# ports.net
KiCad netlist of a schematic drawn in Altium Designer
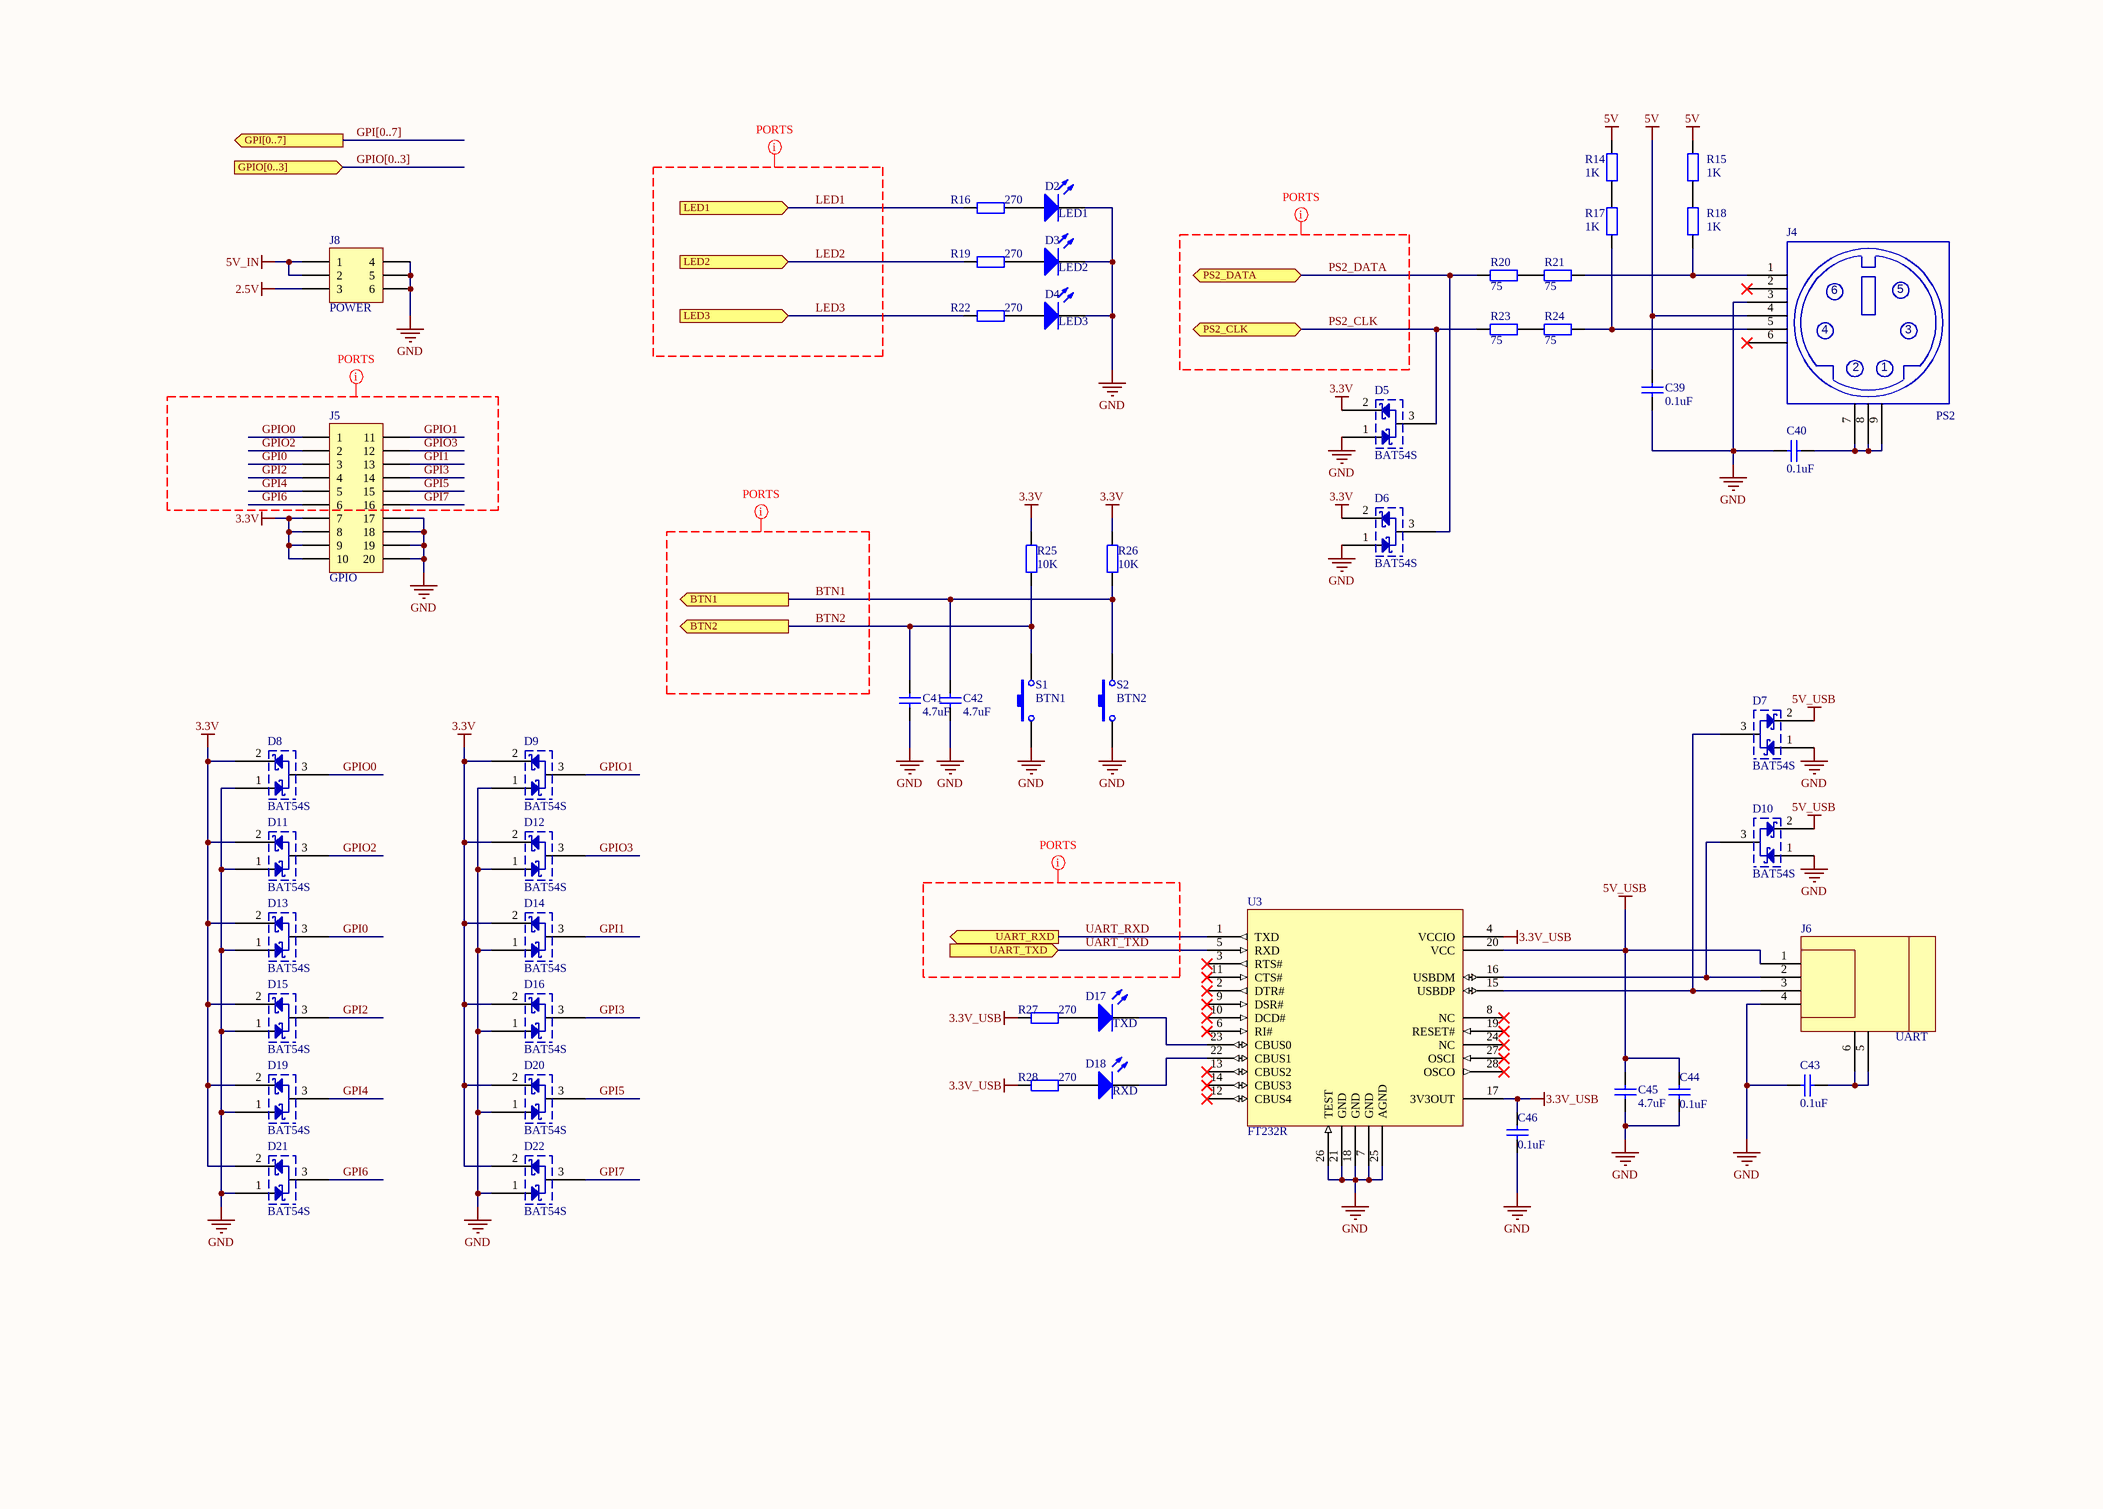
[diagram p0: ports.SchDoc]

(export (version "E")
  (design (tool "Eeschema 10.0.6"))
  (components
    (comp (ref "C39")
      (value "0.1uF")
      (footprint "0402")
      (description "Capacitor")
      (fields (field (name "Comment") "Cap") (field (name "PUBLISHER") "Altium Limited"))
      (libsource (lib "Miscellaneous Devices") (part "Cap"))
    )
    (comp (ref "C40")
      (value "0.1uF")
      (footprint "0402")
      (description "Capacitor")
      (fields (field (name "Comment") "Cap") (field (name "PUBLISHER") "Altium Limited"))
      (libsource (lib "Miscellaneous Devices") (part "Cap"))
    )
    (comp (ref "C41")
      (value "4.7uF")
      (footprint "C0805")
      (description "Capacitor")
      (fields (field (name "Comment") "Cap") (field (name "PUBLISHER") "Altium Limited"))
      (libsource (lib "Miscellaneous Devices") (part "Cap"))
    )
    (comp (ref "C42")
      (value "4.7uF")
      (footprint "C0805")
      (description "Capacitor")
      (fields (field (name "Comment") "Cap") (field (name "PUBLISHER") "Altium Limited"))
      (libsource (lib "Miscellaneous Devices") (part "Cap"))
    )
    (comp (ref "C43")
      (value "0.1uF")
      (footprint "0402")
      (description "Capacitor")
      (fields (field (name "Comment") "Cap") (field (name "PUBLISHER") "Altium Limited"))
      (libsource (lib "Miscellaneous Devices") (part "Cap"))
    )
    (comp (ref "C44")
      (value "0.1uF")
      (footprint "0402")
      (description "Capacitor")
      (fields (field (name "Comment") "Cap") (field (name "PUBLISHER") "Altium Limited"))
      (libsource (lib "Miscellaneous Devices") (part "Cap"))
    )
    (comp (ref "C45")
      (value "4.7uF")
      (footprint "C0805")
      (description "Capacitor")
      (fields (field (name "Comment") "Cap") (field (name "PUBLISHER") "Altium Limited"))
      (libsource (lib "Miscellaneous Devices") (part "Cap"))
    )
    (comp (ref "C46")
      (value "0.1uF")
      (footprint "0402")
      (description "Capacitor")
      (fields (field (name "Comment") "Cap") (field (name "PUBLISHER") "Altium Limited"))
      (libsource (lib "Miscellaneous Devices") (part "Cap"))
    )
    (comp (ref "D2")
      (value "LED1")
      (footprint "LED")
      (description "Amber")
      (fields (field (name "PUBLISHER") "Altium Limited"))
      (libsource (lib "Miscellaneous Devices") (part "LED3"))
    )
    (comp (ref "D3")
      (value "LED2")
      (footprint "LED")
      (description "Amber")
      (fields (field (name "PUBLISHER") "Altium Limited"))
      (libsource (lib "Miscellaneous Devices") (part "LED3"))
    )
    (comp (ref "D4")
      (value "LED3")
      (footprint "LED")
      (description "Amber")
      (fields (field (name "PUBLISHER") "Altium Limited"))
      (libsource (lib "Miscellaneous Devices") (part "LED3"))
    )
    (comp (ref "D5")
      (value "BAT54S")
      (footprint "SOT23_BAT54S")
      (libsource (lib "FPGA_board") (part "BAT54S"))
    )
    (comp (ref "D6")
      (value "BAT54S")
      (footprint "SOT23_BAT54S")
      (libsource (lib "FPGA_board") (part "BAT54S"))
    )
    (comp (ref "D7")
      (value "BAT54S")
      (footprint "SOT23_BAT54S")
      (libsource (lib "FPGA_board") (part "BAT54S"))
    )
    (comp (ref "D8")
      (value "BAT54S")
      (footprint "SOT23_BAT54S")
      (libsource (lib "FPGA_board") (part "BAT54S"))
    )
    (comp (ref "D9")
      (value "BAT54S")
      (footprint "SOT23_BAT54S")
      (libsource (lib "FPGA_board") (part "BAT54S"))
    )
    (comp (ref "D10")
      (value "BAT54S")
      (footprint "SOT23_BAT54S")
      (libsource (lib "FPGA_board") (part "BAT54S"))
    )
    (comp (ref "D11")
      (value "BAT54S")
      (footprint "SOT23_BAT54S")
      (libsource (lib "FPGA_board") (part "BAT54S"))
    )
    (comp (ref "D12")
      (value "BAT54S")
      (footprint "SOT23_BAT54S")
      (libsource (lib "FPGA_board") (part "BAT54S"))
    )
    (comp (ref "D13")
      (value "BAT54S")
      (footprint "SOT23_BAT54S")
      (libsource (lib "FPGA_board") (part "BAT54S"))
    )
    (comp (ref "D14")
      (value "BAT54S")
      (footprint "SOT23_BAT54S")
      (libsource (lib "FPGA_board") (part "BAT54S"))
    )
    (comp (ref "D15")
      (value "BAT54S")
      (footprint "SOT23_BAT54S")
      (libsource (lib "FPGA_board") (part "BAT54S"))
    )
    (comp (ref "D16")
      (value "BAT54S")
      (footprint "SOT23_BAT54S")
      (libsource (lib "FPGA_board") (part "BAT54S"))
    )
    (comp (ref "D17")
      (value "TXD")
      (footprint "LED")
      (description "Green")
      (fields (field (name "PUBLISHER") "Altium Limited"))
      (libsource (lib "Miscellaneous Devices") (part "LED3"))
    )
    (comp (ref "D18")
      (value "RXD")
      (footprint "LED")
      (description "Red")
      (fields (field (name "PUBLISHER") "Altium Limited"))
      (libsource (lib "Miscellaneous Devices") (part "LED3"))
    )
    (comp (ref "D19")
      (value "BAT54S")
      (footprint "SOT23_BAT54S")
      (libsource (lib "FPGA_board") (part "BAT54S"))
    )
    (comp (ref "D20")
      (value "BAT54S")
      (footprint "SOT23_BAT54S")
      (libsource (lib "FPGA_board") (part "BAT54S"))
    )
    (comp (ref "D21")
      (value "BAT54S")
      (footprint "SOT23_BAT54S")
      (libsource (lib "FPGA_board") (part "BAT54S"))
    )
    (comp (ref "D22")
      (value "BAT54S")
      (footprint "SOT23_BAT54S")
      (libsource (lib "FPGA_board") (part "BAT54S"))
    )
    (comp (ref "J4") (value "PS2") (footprint "PS2-6PIN") (libsource (lib "FPGA_board") (part "PS2_Socket")))
    (comp (ref "J5")
      (value "GPIO")
      (footprint "HDR2X10_CEN")
      (description "Header, 10-Pin, Dual row")
      (fields (field (name "PUBLISHER") "Altium Limited"))
      (libsource (lib "Miscellaneous Connectors") (part "Header 10X2A"))
    )
    (comp (ref "J6") (value "UART") (footprint "USB_B") (libsource (lib "FPGA_board") (part "USB_B")))
    (comp (ref "J8")
      (value "POWER")
      (footprint "HDR2X3_CEN")
      (description "Header, 3-Pin, Dual row")
      (fields (field (name "PUBLISHER") "Altium Limited"))
      (libsource (lib "Miscellaneous Connectors") (part "Header 3X2A"))
    )
    (comp (ref "R14")
      (value "1K")
      (footprint "J1-0603")
      (description "Resistor")
      (fields (field (name "Comment") "Res2") (field (name "PUBLISHER") "Altium Limited"))
      (libsource (lib "") (part "Res2_3"))
    )
    (comp (ref "R15")
      (value "1K")
      (footprint "J1-0603")
      (description "Resistor")
      (fields (field (name "Comment") "Res2") (field (name "PUBLISHER") "Altium Limited"))
      (libsource (lib "") (part "Res2_3"))
    )
    (comp (ref "R16")
      (value "270")
      (footprint "6-0805_N")
      (description "Resistor")
      (fields (field (name "Comment") "Res2") (field (name "PUBLISHER") "Altium Limited"))
      (libsource (lib "Miscellaneous Devices") (part "Res2"))
    )
    (comp (ref "R17")
      (value "1K")
      (footprint "J1-0603")
      (description "Resistor")
      (fields (field (name "Comment") "Res2") (field (name "PUBLISHER") "Altium Limited"))
      (libsource (lib "") (part "Res2_3"))
    )
    (comp (ref "R18")
      (value "1K")
      (footprint "J1-0603")
      (description "Resistor")
      (fields (field (name "Comment") "Res2") (field (name "PUBLISHER") "Altium Limited"))
      (libsource (lib "") (part "Res2_3"))
    )
    (comp (ref "R19")
      (value "270")
      (footprint "6-0805_N")
      (description "Resistor")
      (fields (field (name "Comment") "Res2") (field (name "PUBLISHER") "Altium Limited"))
      (libsource (lib "Miscellaneous Devices") (part "Res2"))
    )
    (comp (ref "R20")
      (value "75")
      (footprint "J1-0603")
      (description "Resistor")
      (fields (field (name "Comment") "Res2") (field (name "PUBLISHER") "Altium Limited"))
      (libsource (lib "") (part "Res2_2"))
    )
    (comp (ref "R21")
      (value "75")
      (footprint "J1-0603")
      (description "Resistor")
      (fields (field (name "Comment") "Res2") (field (name "PUBLISHER") "Altium Limited"))
      (libsource (lib "") (part "Res2_2"))
    )
    (comp (ref "R22")
      (value "270")
      (footprint "6-0805_N")
      (description "Resistor")
      (fields (field (name "Comment") "Res2") (field (name "PUBLISHER") "Altium Limited"))
      (libsource (lib "Miscellaneous Devices") (part "Res2"))
    )
    (comp (ref "R23")
      (value "75")
      (footprint "J1-0603")
      (description "Resistor")
      (fields (field (name "Comment") "Res2") (field (name "PUBLISHER") "Altium Limited"))
      (libsource (lib "") (part "Res2_2"))
    )
    (comp (ref "R24")
      (value "75")
      (footprint "J1-0603")
      (description "Resistor")
      (fields (field (name "Comment") "Res2") (field (name "PUBLISHER") "Altium Limited"))
      (libsource (lib "") (part "Res2_2"))
    )
    (comp (ref "R25")
      (value "10K")
      (footprint "J1-0603")
      (description "Resistor")
      (fields (field (name "Comment") "Res2") (field (name "PUBLISHER") "Altium Limited"))
      (libsource (lib "") (part "Res2_1"))
    )
    (comp (ref "R26")
      (value "10K")
      (footprint "J1-0603")
      (description "Resistor")
      (fields (field (name "Comment") "Res2") (field (name "PUBLISHER") "Altium Limited"))
      (libsource (lib "") (part "Res2_1"))
    )
    (comp (ref "R27")
      (value "270")
      (footprint "6-0805_N")
      (description "Resistor")
      (fields (field (name "Comment") "Res2") (field (name "PUBLISHER") "Altium Limited"))
      (libsource (lib "Miscellaneous Devices") (part "Res2"))
    )
    (comp (ref "R28")
      (value "270")
      (footprint "6-0805_N")
      (description "Resistor")
      (fields (field (name "Comment") "Res2") (field (name "PUBLISHER") "Altium Limited"))
      (libsource (lib "Miscellaneous Devices") (part "Res2"))
    )
    (comp (ref "S1")
      (value "BTN1")
      (footprint "PUSHBUTTON")
      (description "Switch")
      (fields (field (name "PUBLISHER") "Altium Limited"))
      (libsource (lib "Miscellaneous Devices") (part "SW-PB"))
    )
    (comp (ref "S2")
      (value "BTN2")
      (footprint "PUSHBUTTON")
      (description "Switch")
      (fields (field (name "PUBLISHER") "Altium Limited"))
      (libsource (lib "Miscellaneous Devices") (part "SW-PB"))
    )
    (comp (ref "U3") (value "FT232R") (footprint "SSOP28") (libsource (lib "FPGA_board") (part "FT232R")))
  )
  (nets
    (net (code "1") (name "/BTN1") (class "Default")
      (node (ref "C42") (pin "2") (pinfunction "2_2") (pintype "passive"))
      (node (ref "R26") (pin "2") (pinfunction "2_2") (pintype "passive"))
      (node (ref "S2") (pin "2") (pinfunction "2_2") (pintype "passive"))
    )
    (net (code "2") (name "/BTN2") (class "Default")
      (node (ref "C41") (pin "2") (pinfunction "2_2") (pintype "passive"))
      (node (ref "R25") (pin "2") (pinfunction "2_2") (pintype "passive"))
      (node (ref "S1") (pin "2") (pinfunction "2_2") (pintype "passive"))
    )
    (net (code "3") (name "/GPI0") (class "Default")
      (node (ref "D13") (pin "3") (pinfunction "3_3") (pintype "passive"))
      (node (ref "J5") (pin "3") (pinfunction "3_3") (pintype "passive"))
    )
    (net (code "4") (name "/GPI1") (class "Default")
      (node (ref "D14") (pin "3") (pinfunction "3_3") (pintype "passive"))
      (node (ref "J5") (pin "13") (pinfunction "13_13") (pintype "passive"))
    )
    (net (code "5") (name "/GPI2") (class "Default")
      (node (ref "D15") (pin "3") (pinfunction "3_3") (pintype "passive"))
      (node (ref "J5") (pin "4") (pinfunction "4_4") (pintype "passive"))
    )
    (net (code "6") (name "/GPI3") (class "Default")
      (node (ref "D16") (pin "3") (pinfunction "3_3") (pintype "passive"))
      (node (ref "J5") (pin "14") (pinfunction "14_14") (pintype "passive"))
    )
    (net (code "7") (name "/GPI4") (class "Default")
      (node (ref "D19") (pin "3") (pinfunction "3_3") (pintype "passive"))
      (node (ref "J5") (pin "5") (pinfunction "5_5") (pintype "passive"))
    )
    (net (code "8") (name "/GPI5") (class "Default")
      (node (ref "D20") (pin "3") (pinfunction "3_3") (pintype "passive"))
      (node (ref "J5") (pin "15") (pinfunction "15_15") (pintype "passive"))
    )
    (net (code "9") (name "/GPI6") (class "Default")
      (node (ref "D21") (pin "3") (pinfunction "3_3") (pintype "passive"))
      (node (ref "J5") (pin "6") (pinfunction "6_6") (pintype "passive"))
    )
    (net (code "10") (name "/GPI7") (class "Default")
      (node (ref "D22") (pin "3") (pinfunction "3_3") (pintype "passive"))
      (node (ref "J5") (pin "16") (pinfunction "16_16") (pintype "passive"))
    )
    (net (code "11") (name "/GPIO0") (class "Default")
      (node (ref "D8") (pin "3") (pinfunction "3_3") (pintype "passive"))
      (node (ref "J5") (pin "1") (pinfunction "1_1") (pintype "passive"))
    )
    (net (code "12") (name "/GPIO1") (class "Default")
      (node (ref "D9") (pin "3") (pinfunction "3_3") (pintype "passive"))
      (node (ref "J5") (pin "11") (pinfunction "11_11") (pintype "passive"))
    )
    (net (code "13") (name "/GPIO2") (class "Default")
      (node (ref "D11") (pin "3") (pinfunction "3_3") (pintype "passive"))
      (node (ref "J5") (pin "2") (pinfunction "2_2") (pintype "passive"))
    )
    (net (code "14") (name "/GPIO3") (class "Default")
      (node (ref "D12") (pin "3") (pinfunction "3_3") (pintype "passive"))
      (node (ref "J5") (pin "12") (pinfunction "12_12") (pintype "passive"))
    )
    (net (code "17") (name "/LED1") (class "Default")
      (node (ref "R16") (pin "2") (pinfunction "2_2") (pintype "passive"))
    )
    (net (code "18") (name "/LED2") (class "Default")
      (node (ref "R19") (pin "2") (pinfunction "2_2") (pintype "passive"))
    )
    (net (code "19") (name "/LED3") (class "Default")
      (node (ref "R22") (pin "2") (pinfunction "2_2") (pintype "passive"))
    )
    (net (code "20") (name "/PS2_CLK") (class "Default")
      (node (ref "D5") (pin "3") (pinfunction "3_3") (pintype "passive"))
      (node (ref "R23") (pin "1") (pinfunction "1_1") (pintype "passive"))
    )
    (net (code "21") (name "/PS2_DATA") (class "Default")
      (node (ref "D6") (pin "3") (pinfunction "3_3") (pintype "passive"))
      (node (ref "R20") (pin "1") (pinfunction "1_1") (pintype "passive"))
    )
    (net (code "22") (name "/UART_RXD") (class "Default")
      (node (ref "U3") (pin "1") (pinfunction "TXD_1") (pintype "output"))
    )
    (net (code "23") (name "/UART_TXD") (class "Default")
      (node (ref "U3") (pin "5") (pinfunction "RXD_5") (pintype "input"))
    )
    (net (code "24") (name "2.5V") (class "Default")
      (node (ref "J8") (pin "3") (pinfunction "3_3") (pintype "passive"))
    )
    (net (code "25") (name "3.3V") (class "Default")
      (node (ref "D11") (pin "2") (pinfunction "2_2") (pintype "passive"))
      (node (ref "D12") (pin "2") (pinfunction "2_2") (pintype "passive"))
      (node (ref "D13") (pin "2") (pinfunction "2_2") (pintype "passive"))
      (node (ref "D14") (pin "2") (pinfunction "2_2") (pintype "passive"))
      (node (ref "D15") (pin "2") (pinfunction "2_2") (pintype "passive"))
      (node (ref "D16") (pin "2") (pinfunction "2_2") (pintype "passive"))
      (node (ref "D19") (pin "2") (pinfunction "2_2") (pintype "passive"))
      (node (ref "D20") (pin "2") (pinfunction "2_2") (pintype "passive"))
      (node (ref "D21") (pin "2") (pinfunction "2_2") (pintype "passive"))
      (node (ref "D22") (pin "2") (pinfunction "2_2") (pintype "passive"))
      (node (ref "D5") (pin "2") (pinfunction "2_2") (pintype "passive"))
      (node (ref "D6") (pin "2") (pinfunction "2_2") (pintype "passive"))
      (node (ref "D8") (pin "2") (pinfunction "2_2") (pintype "passive"))
      (node (ref "D9") (pin "2") (pinfunction "2_2") (pintype "passive"))
      (node (ref "J5") (pin "10") (pinfunction "10_10") (pintype "passive"))
      (node (ref "J5") (pin "7") (pinfunction "7_7") (pintype "passive"))
      (node (ref "J5") (pin "8") (pinfunction "8_8") (pintype "passive"))
      (node (ref "J5") (pin "9") (pinfunction "9_9") (pintype "passive"))
      (node (ref "R25") (pin "1") (pinfunction "1_1") (pintype "passive"))
      (node (ref "R26") (pin "1") (pinfunction "1_1") (pintype "passive"))
    )
    (net (code "26") (name "3.3V_USB") (class "Default")
      (node (ref "C46") (pin "1") (pinfunction "1_1") (pintype "passive"))
      (node (ref "R27") (pin "2") (pinfunction "2_2") (pintype "passive"))
      (node (ref "R28") (pin "2") (pinfunction "2_2") (pintype "passive"))
      (node (ref "U3") (pin "17") (pinfunction "3V3OUT_17") (pintype "power_in"))
      (node (ref "U3") (pin "4") (pinfunction "VCCIO_4") (pintype "power_in"))
    )
    (net (code "27") (name "5V") (class "Default")
      (node (ref "C39") (pin "2") (pinfunction "2_2") (pintype "passive"))
      (node (ref "J4") (pin "4") (pintype "passive"))
      (node (ref "R14") (pin "2") (pinfunction "2_2") (pintype "passive"))
      (node (ref "R15") (pin "2") (pinfunction "2_2") (pintype "passive"))
    )
    (net (code "28") (name "5V_IN") (class "Default")
      (node (ref "J8") (pin "1") (pinfunction "1_1") (pintype "passive"))
      (node (ref "J8") (pin "2") (pinfunction "2_2") (pintype "passive"))
    )
    (net (code "29") (name "5V_USB") (class "Default")
      (node (ref "C44") (pin "1") (pinfunction "1_1") (pintype "passive"))
      (node (ref "C45") (pin "2") (pinfunction "2_2") (pintype "passive"))
      (node (ref "D10") (pin "2") (pinfunction "2_2") (pintype "passive"))
      (node (ref "D7") (pin "2") (pinfunction "2_2") (pintype "passive"))
      (node (ref "J6") (pin "1") (pintype "passive"))
      (node (ref "U3") (pin "20") (pinfunction "VCC_20") (pintype "power_in"))
    )
    (net (code "30") (name "GND") (class "Default")
      (node (ref "C39") (pin "1") (pinfunction "1_1") (pintype "passive"))
      (node (ref "C40") (pin "1") (pinfunction "1_1") (pintype "passive"))
      (node (ref "C41") (pin "1") (pinfunction "1_1") (pintype "passive"))
      (node (ref "C42") (pin "1") (pinfunction "1_1") (pintype "passive"))
      (node (ref "C43") (pin "1") (pinfunction "1_1") (pintype "passive"))
      (node (ref "C44") (pin "2") (pinfunction "2_2") (pintype "passive"))
      (node (ref "C45") (pin "1") (pinfunction "1_1") (pintype "passive"))
      (node (ref "C46") (pin "2") (pinfunction "2_2") (pintype "passive"))
      (node (ref "D10") (pin "1") (pinfunction "1_1") (pintype "passive"))
      (node (ref "D11") (pin "1") (pinfunction "1_1") (pintype "passive"))
      (node (ref "D12") (pin "1") (pinfunction "1_1") (pintype "passive"))
      (node (ref "D13") (pin "1") (pinfunction "1_1") (pintype "passive"))
      (node (ref "D14") (pin "1") (pinfunction "1_1") (pintype "passive"))
      (node (ref "D15") (pin "1") (pinfunction "1_1") (pintype "passive"))
      (node (ref "D16") (pin "1") (pinfunction "1_1") (pintype "passive"))
      (node (ref "D19") (pin "1") (pinfunction "1_1") (pintype "passive"))
      (node (ref "D2") (pin "2") (pinfunction "K_2") (pintype "passive"))
      (node (ref "D20") (pin "1") (pinfunction "1_1") (pintype "passive"))
      (node (ref "D21") (pin "1") (pinfunction "1_1") (pintype "passive"))
      (node (ref "D22") (pin "1") (pinfunction "1_1") (pintype "passive"))
      (node (ref "D3") (pin "2") (pinfunction "K_2") (pintype "passive"))
      (node (ref "D4") (pin "2") (pinfunction "K_2") (pintype "passive"))
      (node (ref "D5") (pin "1") (pinfunction "1_1") (pintype "passive"))
      (node (ref "D6") (pin "1") (pinfunction "1_1") (pintype "passive"))
      (node (ref "D7") (pin "1") (pinfunction "1_1") (pintype "passive"))
      (node (ref "D8") (pin "1") (pinfunction "1_1") (pintype "passive"))
      (node (ref "D9") (pin "1") (pinfunction "1_1") (pintype "passive"))
      (node (ref "J4") (pin "3") (pintype "passive"))
      (node (ref "J5") (pin "17") (pinfunction "17_17") (pintype "passive"))
      (node (ref "J5") (pin "18") (pinfunction "18_18") (pintype "passive"))
      (node (ref "J5") (pin "19") (pinfunction "19_19") (pintype "passive"))
      (node (ref "J5") (pin "20") (pinfunction "20_20") (pintype "passive"))
      (node (ref "J6") (pin "4") (pintype "passive"))
      (node (ref "J8") (pin "4") (pinfunction "4_4") (pintype "passive"))
      (node (ref "J8") (pin "5") (pinfunction "5_5") (pintype "passive"))
      (node (ref "J8") (pin "6") (pinfunction "6_6") (pintype "passive"))
      (node (ref "S1") (pin "1") (pinfunction "1_1") (pintype "passive"))
      (node (ref "S2") (pin "1") (pinfunction "1_1") (pintype "passive"))
      (node (ref "U3") (pin "18") (pinfunction "GND_18") (pintype "power_in"))
      (node (ref "U3") (pin "21") (pinfunction "GND_21") (pintype "power_in"))
      (node (ref "U3") (pin "25") (pinfunction "AGND_25") (pintype "power_in"))
      (node (ref "U3") (pin "26") (pinfunction "TEST_26") (pintype "input"))
      (node (ref "U3") (pin "7") (pinfunction "GND_7") (pintype "power_in"))
    )
    (net (code "31") (name "Net-(C40-Pad2)") (class "Default")
      (node (ref "C40") (pin "2") (pinfunction "2_2") (pintype "passive"))
      (node (ref "J4") (pin "7") (pintype "passive"))
      (node (ref "J4") (pin "8") (pintype "passive"))
      (node (ref "J4") (pin "9") (pintype "passive"))
    )
    (net (code "32") (name "Net-(C43-Pad2)") (class "Default")
      (node (ref "C43") (pin "2") (pinfunction "2_2") (pintype "passive"))
      (node (ref "J6") (pin "5") (pintype "passive"))
      (node (ref "J6") (pin "6") (pintype "passive"))
    )
    (net (code "33") (name "Net-(D2-A)") (class "Default")
      (node (ref "D2") (pin "1") (pinfunction "A_1") (pintype "passive"))
      (node (ref "R16") (pin "1") (pinfunction "1_1") (pintype "passive"))
    )
    (net (code "34") (name "Net-(D3-A)") (class "Default")
      (node (ref "D3") (pin "1") (pinfunction "A_1") (pintype "passive"))
      (node (ref "R19") (pin "1") (pinfunction "1_1") (pintype "passive"))
    )
    (net (code "35") (name "Net-(D4-A)") (class "Default")
      (node (ref "D4") (pin "1") (pinfunction "A_1") (pintype "passive"))
      (node (ref "R22") (pin "1") (pinfunction "1_1") (pintype "passive"))
    )
    (net (code "36") (name "Net-(D17-A)") (class "Default")
      (node (ref "D17") (pin "1") (pinfunction "A_1") (pintype "passive"))
      (node (ref "R27") (pin "1") (pinfunction "1_1") (pintype "passive"))
    )
    (net (code "37") (name "Net-(D17-K)") (class "Default")
      (node (ref "D17") (pin "2") (pinfunction "K_2") (pintype "passive"))
      (node (ref "U3") (pin "23") (pinfunction "CBUS0_23") (pintype "bidirectional"))
    )
    (net (code "38") (name "Net-(D18-A)") (class "Default")
      (node (ref "D18") (pin "1") (pinfunction "A_1") (pintype "passive"))
      (node (ref "R28") (pin "1") (pinfunction "1_1") (pintype "passive"))
    )
    (net (code "39") (name "Net-(D18-K)") (class "Default")
      (node (ref "D18") (pin "2") (pinfunction "K_2") (pintype "passive"))
      (node (ref "U3") (pin "22") (pinfunction "CBUS1_22") (pintype "bidirectional"))
    )
    (net (code "40") (name "Net-(J4-Pad1)") (class "Default")
      (node (ref "J4") (pin "1") (pintype "passive"))
      (node (ref "R18") (pin "1") (pinfunction "1_1") (pintype "passive"))
      (node (ref "R21") (pin "2") (pinfunction "2_2") (pintype "passive"))
    )
    (net (code "41") (name "Net-(J4-Pad5)") (class "Default")
      (node (ref "J4") (pin "5") (pintype "passive"))
      (node (ref "R17") (pin "1") (pinfunction "1_1") (pintype "passive"))
      (node (ref "R24") (pin "2") (pinfunction "2_2") (pintype "passive"))
    )
    (net (code "42") (name "Net-(R14-Pad1)") (class "Default")
      (node (ref "R14") (pin "1") (pinfunction "1_1") (pintype "passive"))
      (node (ref "R17") (pin "2") (pinfunction "2_2") (pintype "passive"))
    )
    (net (code "43") (name "Net-(R15-Pad1)") (class "Default")
      (node (ref "R15") (pin "1") (pinfunction "1_1") (pintype "passive"))
      (node (ref "R18") (pin "2") (pinfunction "2_2") (pintype "passive"))
    )
    (net (code "44") (name "Net-(R20-Pad2)") (class "Default")
      (node (ref "R20") (pin "2") (pinfunction "2_2") (pintype "passive"))
      (node (ref "R21") (pin "1") (pinfunction "1_1") (pintype "passive"))
    )
    (net (code "45") (name "Net-(R23-Pad2)") (class "Default")
      (node (ref "R23") (pin "2") (pinfunction "2_2") (pintype "passive"))
      (node (ref "R24") (pin "1") (pinfunction "1_1") (pintype "passive"))
    )
    (net (code "46") (name "Net-(U3-USBDM)") (class "Default")
      (node (ref "D10") (pin "3") (pinfunction "3_3") (pintype "passive"))
      (node (ref "J6") (pin "2") (pintype "passive"))
      (node (ref "U3") (pin "16") (pinfunction "USBDM_16") (pintype "bidirectional"))
    )
    (net (code "47") (name "Net-(U3-USBDP)") (class "Default")
      (node (ref "D7") (pin "3") (pinfunction "3_3") (pintype "passive"))
      (node (ref "J6") (pin "3") (pintype "passive"))
      (node (ref "U3") (pin "15") (pinfunction "USBDP_15") (pintype "bidirectional"))
    )
    (net (code "48") (name "unconnected-(J4-Pad2)") (class "Default")
      (node (ref "J4") (pin "2") (pintype "passive+no_connect"))
    )
    (net (code "49") (name "unconnected-(J4-Pad6)") (class "Default")
      (node (ref "J4") (pin "6") (pintype "passive+no_connect"))
    )
    (net (code "50") (name "unconnected-(U3-CBUS2-Pad13)") (class "Default")
      (node (ref "U3") (pin "13") (pinfunction "CBUS2_13") (pintype "bidirectional+no_connect"))
    )
    (net (code "51") (name "unconnected-(U3-CBUS3-Pad14)") (class "Default")
      (node (ref "U3") (pin "14") (pinfunction "CBUS3_14") (pintype "bidirectional+no_connect"))
    )
    (net (code "52") (name "unconnected-(U3-CBUS4-Pad12)") (class "Default")
      (node (ref "U3") (pin "12") (pinfunction "CBUS4_12") (pintype "bidirectional+no_connect"))
    )
    (net (code "53") (name "unconnected-(U3-CTS#-Pad11)") (class "Default")
      (node (ref "U3") (pin "11") (pinfunction "CTS#_11") (pintype "input+no_connect"))
    )
    (net (code "54") (name "unconnected-(U3-DCD#-Pad10)") (class "Default")
      (node (ref "U3") (pin "10") (pinfunction "DCD#_10") (pintype "input+no_connect"))
    )
    (net (code "55") (name "unconnected-(U3-DSR#-Pad9)") (class "Default")
      (node (ref "U3") (pin "9") (pinfunction "DSR#_9") (pintype "input+no_connect"))
    )
    (net (code "56") (name "unconnected-(U3-DTR#-Pad2)") (class "Default")
      (node (ref "U3") (pin "2") (pinfunction "DTR#_2") (pintype "output+no_connect"))
    )
    (net (code "57") (name "unconnected-(U3-NC-Pad8)") (class "Default")
      (node (ref "U3") (pin "8") (pinfunction "NC_8") (pintype "passive+no_connect"))
    )
    (net (code "58") (name "unconnected-(U3-NC-Pad24)") (class "Default")
      (node (ref "U3") (pin "24") (pinfunction "NC_24") (pintype "passive+no_connect"))
    )
    (net (code "59") (name "unconnected-(U3-OSCI-Pad27)") (class "Default")
      (node (ref "U3") (pin "27") (pinfunction "OSCI_27") (pintype "input+no_connect"))
    )
    (net (code "60") (name "unconnected-(U3-OSCO-Pad28)") (class "Default")
      (node (ref "U3") (pin "28") (pinfunction "OSCO_28") (pintype "output+no_connect"))
    )
    (net (code "61") (name "unconnected-(U3-RESET#-Pad19)") (class "Default")
      (node (ref "U3") (pin "19") (pinfunction "RESET#_19") (pintype "input+no_connect"))
    )
    (net (code "62") (name "unconnected-(U3-RI#-Pad6)") (class "Default")
      (node (ref "U3") (pin "6") (pinfunction "RI#_6") (pintype "input+no_connect"))
    )
    (net (code "63") (name "unconnected-(U3-RTS#-Pad3)") (class "Default")
      (node (ref "U3") (pin "3") (pinfunction "RTS#_3") (pintype "output+no_connect"))
    )
  )
)
